# MXT2088.net
KiCad netlist of a schematic drawn in Altium Designer
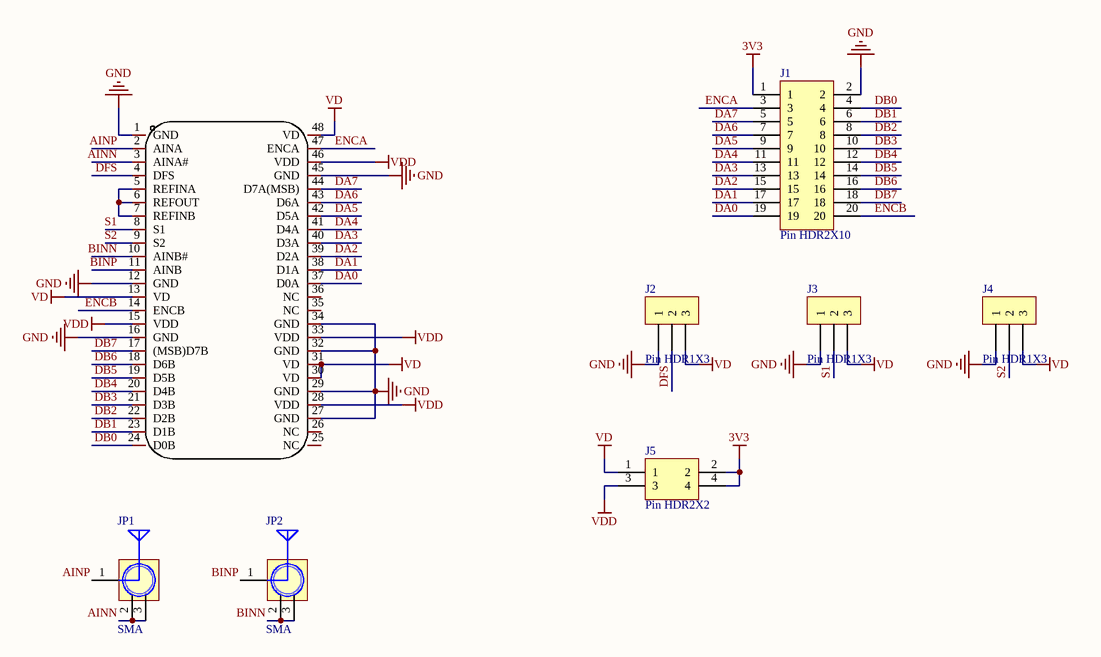
[diagram p0: MXT2088.SchDoc]

(export (version "E")
  (design (tool "Eeschema 10.0.6"))
  (components
    (comp (ref "J1")
      (value "Pin HDR2X10")
      (footprint "Pin HDR2X10/2.54mm-S")
      (libsource (lib "排针") (part "Pin HDR2X10"))
    )
    (comp (ref "J2")
      (value "Pin HDR1X3")
      (footprint "Pin HDR1X3/2.54mm-S")
      (libsource (lib "排针") (part "Pin HDR1X3"))
    )
    (comp (ref "J3")
      (value "Pin HDR1X3")
      (footprint "Pin HDR1X3/2.54mm-S")
      (libsource (lib "排针") (part "Pin HDR1X3"))
    )
    (comp (ref "J4")
      (value "Pin HDR1X3")
      (footprint "Pin HDR1X3/2.54mm-S")
      (libsource (lib "排针") (part "Pin HDR1X3"))
    )
    (comp (ref "J5")
      (value "Pin HDR2X2")
      (footprint "Pin HDR2X2/2.54mm-S")
      (libsource (lib "排针") (part "Pin HDR2X2"))
    )
    (comp (ref "JP1")
      (value "SMA")
      (footprint "SMA-KE")
      (description "SMA-2.4G射频天线接口")
      (fields (field (name "版权归属") "源创客"))
      (libsource (lib "MXT2088") (part "SMA"))
    )
    (comp (ref "JP2")
      (value "SMA")
      (footprint "SMA-KE")
      (description "SMA-2.4G射频天线接口")
      (fields (field (name "版权归属") "源创客"))
      (libsource (lib "MXT2088") (part "SMA"))
    )
    (comp (ref "U1")
      (value "AD9288BSTZ-40")
      (footprint "LQFP-48_L7.0-W7.0-P0.50-LS9.0-BL")
      (fields (field (name "MANUFACTURER") "ADI(亚德诺)"))
      (libsource (lib "MXT2088") (part "AD9288BSTZ-40"))
    )
  )
  (nets
    (net (code "1") (name "/AINN") (class "Default")
      (node (ref "JP1") (pin "2") (pinfunction "GND_2") (pintype "passive"))
      (node (ref "JP1") (pin "3") (pinfunction "GND_3") (pintype "passive"))
      (node (ref "U1") (pin "3") (pinfunction "AINA#_3") (pintype "passive"))
    )
    (net (code "2") (name "/AINP") (class "Default")
      (node (ref "JP1") (pin "1") (pinfunction "ANT_1") (pintype "passive"))
      (node (ref "U1") (pin "2") (pinfunction "AINA_2") (pintype "passive"))
    )
    (net (code "3") (name "/BINN") (class "Default")
      (node (ref "JP2") (pin "2") (pinfunction "GND_2") (pintype "passive"))
      (node (ref "JP2") (pin "3") (pinfunction "GND_3") (pintype "passive"))
      (node (ref "U1") (pin "10") (pinfunction "AINB#_10") (pintype "passive"))
    )
    (net (code "4") (name "/BINP") (class "Default")
      (node (ref "JP2") (pin "1") (pinfunction "ANT_1") (pintype "passive"))
      (node (ref "U1") (pin "11") (pinfunction "AINB_11") (pintype "passive"))
    )
    (net (code "5") (name "/DA0") (class "Default")
      (node (ref "J1") (pin "19") (pinfunction "19_19") (pintype "passive"))
      (node (ref "U1") (pin "37") (pinfunction "D0A_37") (pintype "passive"))
    )
    (net (code "6") (name "/DA1") (class "Default")
      (node (ref "J1") (pin "17") (pinfunction "17_17") (pintype "passive"))
      (node (ref "U1") (pin "38") (pinfunction "D1A_38") (pintype "passive"))
    )
    (net (code "7") (name "/DA2") (class "Default")
      (node (ref "J1") (pin "15") (pinfunction "15_15") (pintype "passive"))
      (node (ref "U1") (pin "39") (pinfunction "D2A_39") (pintype "passive"))
    )
    (net (code "8") (name "/DA3") (class "Default")
      (node (ref "J1") (pin "13") (pinfunction "13_13") (pintype "passive"))
      (node (ref "U1") (pin "40") (pinfunction "D3A_40") (pintype "passive"))
    )
    (net (code "9") (name "/DA4") (class "Default")
      (node (ref "J1") (pin "11") (pinfunction "11_11") (pintype "passive"))
      (node (ref "U1") (pin "41") (pinfunction "D4A_41") (pintype "passive"))
    )
    (net (code "10") (name "/DA5") (class "Default")
      (node (ref "J1") (pin "9") (pinfunction "9_9") (pintype "passive"))
      (node (ref "U1") (pin "42") (pinfunction "D5A_42") (pintype "passive"))
    )
    (net (code "11") (name "/DA6") (class "Default")
      (node (ref "J1") (pin "7") (pinfunction "7_7") (pintype "passive"))
      (node (ref "U1") (pin "43") (pinfunction "D6A_43") (pintype "passive"))
    )
    (net (code "12") (name "/DA7") (class "Default")
      (node (ref "J1") (pin "5") (pinfunction "5_5") (pintype "passive"))
      (node (ref "U1") (pin "44") (pinfunction "D7A(MSB)_44") (pintype "passive"))
    )
    (net (code "13") (name "/DB0") (class "Default")
      (node (ref "J1") (pin "4") (pinfunction "4_4") (pintype "passive"))
      (node (ref "U1") (pin "24") (pinfunction "D0B_24") (pintype "passive"))
    )
    (net (code "14") (name "/DB1") (class "Default")
      (node (ref "J1") (pin "6") (pinfunction "6_6") (pintype "passive"))
      (node (ref "U1") (pin "23") (pinfunction "D1B_23") (pintype "passive"))
    )
    (net (code "15") (name "/DB2") (class "Default")
      (node (ref "J1") (pin "8") (pinfunction "8_8") (pintype "passive"))
      (node (ref "U1") (pin "22") (pinfunction "D2B_22") (pintype "passive"))
    )
    (net (code "16") (name "/DB3") (class "Default")
      (node (ref "J1") (pin "10") (pinfunction "10_10") (pintype "passive"))
      (node (ref "U1") (pin "21") (pinfunction "D3B_21") (pintype "passive"))
    )
    (net (code "17") (name "/DB4") (class "Default")
      (node (ref "J1") (pin "12") (pinfunction "12_12") (pintype "passive"))
      (node (ref "U1") (pin "20") (pinfunction "D4B_20") (pintype "passive"))
    )
    (net (code "18") (name "/DB5") (class "Default")
      (node (ref "J1") (pin "14") (pinfunction "14_14") (pintype "passive"))
      (node (ref "U1") (pin "19") (pinfunction "D5B_19") (pintype "passive"))
    )
    (net (code "19") (name "/DB6") (class "Default")
      (node (ref "J1") (pin "16") (pinfunction "16_16") (pintype "passive"))
      (node (ref "U1") (pin "18") (pinfunction "D6B_18") (pintype "passive"))
    )
    (net (code "20") (name "/DB7") (class "Default")
      (node (ref "J1") (pin "18") (pinfunction "18_18") (pintype "passive"))
      (node (ref "U1") (pin "17") (pinfunction "(MSB)D7B_17") (pintype "passive"))
    )
    (net (code "21") (name "/DFS") (class "Default")
      (node (ref "J2") (pin "2") (pinfunction "2_2") (pintype "passive"))
      (node (ref "U1") (pin "4") (pinfunction "DFS_4") (pintype "passive"))
    )
    (net (code "22") (name "/ENCA") (class "Default")
      (node (ref "J1") (pin "3") (pinfunction "3_3") (pintype "passive"))
      (node (ref "U1") (pin "47") (pinfunction "ENCA_47") (pintype "passive"))
    )
    (net (code "23") (name "/ENCB") (class "Default")
      (node (ref "J1") (pin "20") (pinfunction "20_20") (pintype "passive"))
      (node (ref "U1") (pin "14") (pinfunction "ENCB_14") (pintype "passive"))
    )
    (net (code "24") (name "/S1") (class "Default")
      (node (ref "J3") (pin "2") (pinfunction "2_2") (pintype "passive"))
      (node (ref "U1") (pin "8") (pinfunction "S1_8") (pintype "passive"))
    )
    (net (code "25") (name "/S2") (class "Default")
      (node (ref "J4") (pin "2") (pinfunction "2_2") (pintype "passive"))
      (node (ref "U1") (pin "9") (pinfunction "S2_9") (pintype "passive"))
    )
    (net (code "26") (name "3V3") (class "Default")
      (node (ref "J1") (pin "1") (pinfunction "1_1") (pintype "passive"))
      (node (ref "J5") (pin "2") (pinfunction "2_2") (pintype "passive"))
      (node (ref "J5") (pin "4") (pinfunction "4_4") (pintype "passive"))
    )
    (net (code "27") (name "GND") (class "Default")
      (node (ref "J1") (pin "2") (pinfunction "2_2") (pintype "passive"))
      (node (ref "J2") (pin "1") (pinfunction "1_1") (pintype "passive"))
      (node (ref "J3") (pin "1") (pinfunction "1_1") (pintype "passive"))
      (node (ref "J4") (pin "1") (pinfunction "1_1") (pintype "passive"))
      (node (ref "U1") (pin "1") (pinfunction "GND_1") (pintype "passive"))
      (node (ref "U1") (pin "12") (pinfunction "GND_12") (pintype "passive"))
      (node (ref "U1") (pin "16") (pinfunction "GND_16") (pintype "passive"))
      (node (ref "U1") (pin "27") (pinfunction "GND_27") (pintype "passive"))
      (node (ref "U1") (pin "29") (pinfunction "GND_29") (pintype "passive"))
      (node (ref "U1") (pin "32") (pinfunction "GND_32") (pintype "passive"))
      (node (ref "U1") (pin "34") (pinfunction "GND_34") (pintype "passive"))
      (node (ref "U1") (pin "45") (pinfunction "GND_45") (pintype "passive"))
    )
    (net (code "28") (name "Net-(U1-REFINA)") (class "Default")
      (node (ref "U1") (pin "5") (pinfunction "REFINA_5") (pintype "passive"))
      (node (ref "U1") (pin "6") (pinfunction "REFOUT_6") (pintype "passive"))
      (node (ref "U1") (pin "7") (pinfunction "REFINB_7") (pintype "passive"))
    )
    (net (code "29") (name "VD") (class "Default")
      (node (ref "J2") (pin "3") (pinfunction "3_3") (pintype "passive"))
      (node (ref "J3") (pin "3") (pinfunction "3_3") (pintype "passive"))
      (node (ref "J4") (pin "3") (pinfunction "3_3") (pintype "passive"))
      (node (ref "J5") (pin "1") (pinfunction "1_1") (pintype "passive"))
      (node (ref "U1") (pin "13") (pinfunction "VD_13") (pintype "passive"))
      (node (ref "U1") (pin "30") (pinfunction "VD_30") (pintype "passive"))
      (node (ref "U1") (pin "31") (pinfunction "VD_31") (pintype "passive"))
      (node (ref "U1") (pin "48") (pinfunction "VD_48") (pintype "passive"))
    )
    (net (code "30") (name "VDD") (class "Default")
      (node (ref "J5") (pin "3") (pinfunction "3_3") (pintype "passive"))
      (node (ref "U1") (pin "15") (pinfunction "VDD_15") (pintype "passive"))
      (node (ref "U1") (pin "28") (pinfunction "VDD_28") (pintype "passive"))
      (node (ref "U1") (pin "33") (pinfunction "VDD_33") (pintype "passive"))
      (node (ref "U1") (pin "46") (pinfunction "VDD_46") (pintype "passive"))
    )
    (net (code "31") (name "unconnected-(U1-NC-Pad25)") (class "Default")
      (node (ref "U1") (pin "25") (pinfunction "NC_25") (pintype "passive"))
    )
    (net (code "32") (name "unconnected-(U1-NC-Pad26)") (class "Default")
      (node (ref "U1") (pin "26") (pinfunction "NC_26") (pintype "passive"))
    )
    (net (code "33") (name "unconnected-(U1-NC-Pad35)") (class "Default")
      (node (ref "U1") (pin "35") (pinfunction "NC_35") (pintype "passive"))
    )
    (net (code "34") (name "unconnected-(U1-NC-Pad36)") (class "Default")
      (node (ref "U1") (pin "36") (pinfunction "NC_36") (pintype "passive"))
    )
  )
)
